# Sound.net
KiCad netlist of a schematic drawn in EAGLE
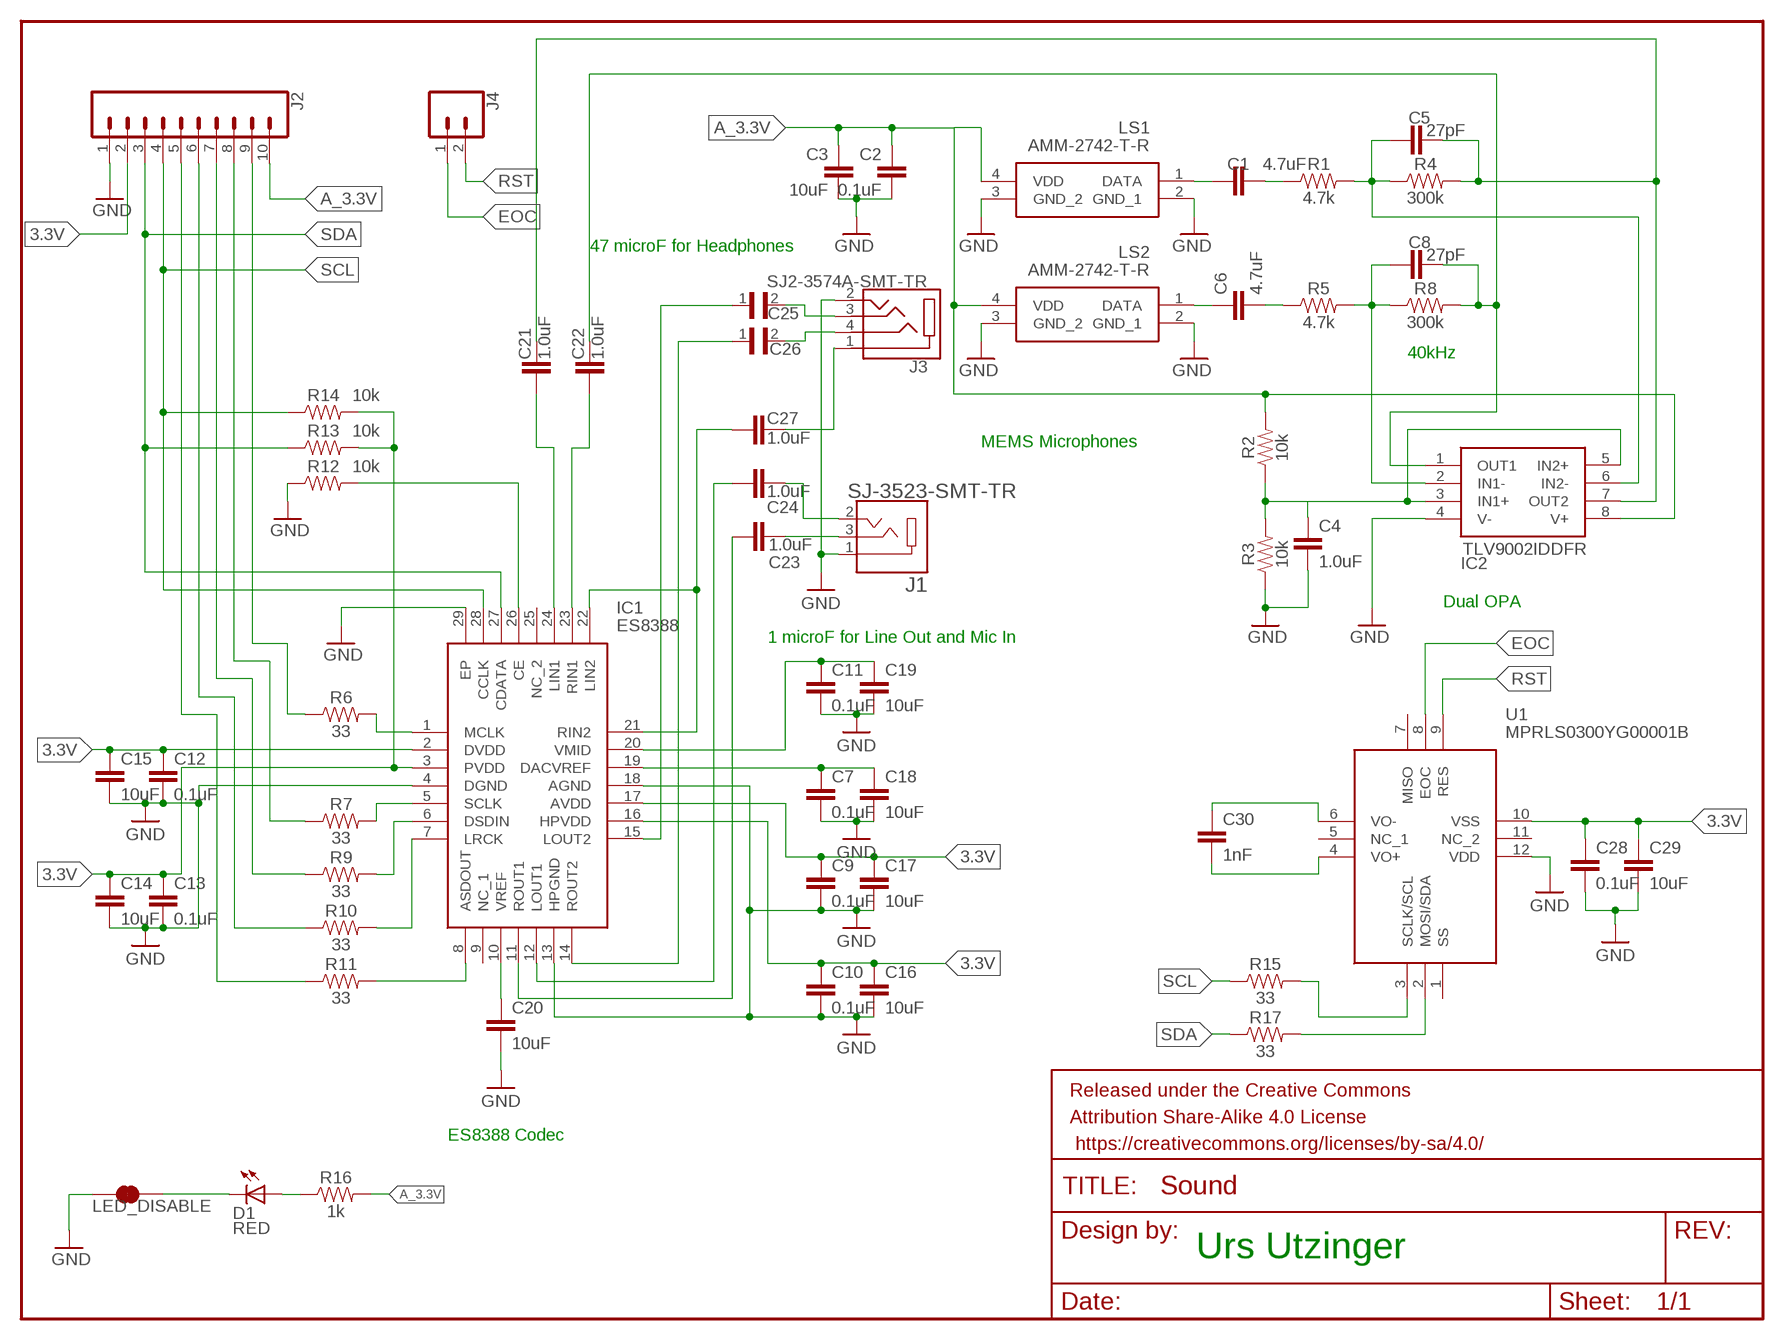
[diagram p0: schematic, sheet 1]

(export (version "E")
  (design (tool "Eeschema 10.0.6"))
  (components
    (comp (ref "C1")
      (value "4.7uF")
      (footprint "eagle-import:0603")
      (libsource (lib "eagle-import") (part "4.7UF-0603-6.3V-(10%)"))
    )
    (comp (ref "C2")
      (value "0.1uF")
      (footprint "eagle-import:0603")
      (libsource (lib "eagle-import") (part "0.1UF-0603-25V-5%"))
    )
    (comp (ref "C3")
      (value "10uF")
      (footprint "eagle-import:0603")
      (libsource (lib "eagle-import") (part "10UF-0603-6.3V-20%"))
    )
    (comp (ref "C4")
      (value "1.0uF")
      (footprint "eagle-import:0603")
      (libsource (lib "eagle-import") (part "1.0UF-0603-16V-10%"))
    )
    (comp (ref "C5")
      (value "27pF")
      (footprint "eagle-import:0603")
      (libsource (lib "eagle-import") (part "27PF-0603-50V-5%"))
    )
    (comp (ref "C6")
      (value "4.7uF")
      (footprint "eagle-import:0603")
      (libsource (lib "eagle-import") (part "4.7UF-0603-6.3V-(10%)"))
    )
    (comp (ref "C7")
      (value "0.1uF")
      (footprint "eagle-import:0603")
      (libsource (lib "eagle-import") (part "0.1UF-0603-25V-5%"))
    )
    (comp (ref "C8")
      (value "27pF")
      (footprint "eagle-import:0603")
      (libsource (lib "eagle-import") (part "27PF-0603-50V-5%"))
    )
    (comp (ref "C9")
      (value "0.1uF")
      (footprint "eagle-import:0603")
      (libsource (lib "eagle-import") (part "0.1UF-0603-25V-5%"))
    )
    (comp (ref "C10")
      (value "0.1uF")
      (footprint "eagle-import:0603")
      (libsource (lib "eagle-import") (part "0.1UF-0603-25V-5%"))
    )
    (comp (ref "C11")
      (value "0.1uF")
      (footprint "eagle-import:0603")
      (libsource (lib "eagle-import") (part "0.1UF-0603-25V-5%"))
    )
    (comp (ref "C12")
      (value "0.1uF")
      (footprint "eagle-import:0603")
      (libsource (lib "eagle-import") (part "0.1UF-0603-25V-5%"))
    )
    (comp (ref "C13")
      (value "0.1uF")
      (footprint "eagle-import:0603")
      (libsource (lib "eagle-import") (part "0.1UF-0603-25V-5%"))
    )
    (comp (ref "C14")
      (value "10uF")
      (footprint "eagle-import:0603")
      (libsource (lib "eagle-import") (part "10UF-0603-6.3V-20%"))
    )
    (comp (ref "C15")
      (value "10uF")
      (footprint "eagle-import:0603")
      (libsource (lib "eagle-import") (part "10UF-0603-6.3V-20%"))
    )
    (comp (ref "C16")
      (value "10uF")
      (footprint "eagle-import:0603")
      (libsource (lib "eagle-import") (part "10UF-0603-6.3V-20%"))
    )
    (comp (ref "C17")
      (value "10uF")
      (footprint "eagle-import:0603")
      (libsource (lib "eagle-import") (part "10UF-0603-6.3V-20%"))
    )
    (comp (ref "C18")
      (value "10uF")
      (footprint "eagle-import:0603")
      (libsource (lib "eagle-import") (part "10UF-0603-6.3V-20%"))
    )
    (comp (ref "C19")
      (value "10uF")
      (footprint "eagle-import:0603")
      (libsource (lib "eagle-import") (part "10UF-0603-6.3V-20%"))
    )
    (comp (ref "C20")
      (value "10uF")
      (footprint "eagle-import:0603")
      (libsource (lib "eagle-import") (part "10UF-0603-6.3V-20%"))
    )
    (comp (ref "C21")
      (value "1.0uF")
      (footprint "eagle-import:0603")
      (libsource (lib "eagle-import") (part "1.0UF-0603-16V-10%"))
    )
    (comp (ref "C22")
      (value "1.0uF")
      (footprint "eagle-import:0603")
      (libsource (lib "eagle-import") (part "1.0UF-0603-16V-10%"))
    )
    (comp (ref "C23")
      (value "1.0uF")
      (footprint "eagle-import:0603")
      (libsource (lib "eagle-import") (part "1.0UF-0603-16V-10%"))
    )
    (comp (ref "C24")
      (value "1.0uF")
      (footprint "eagle-import:0603")
      (libsource (lib "eagle-import") (part "1.0UF-0603-16V-10%"))
    )
    (comp (ref "C25")
      (value "GRM188R60J476ME15D")
      (footprint "eagle-import:CAPC1608X100N")
      (libsource (lib "eagle-import") (part "GRM188R60J476ME15D"))
    )
    (comp (ref "C26")
      (value "GRM188R60J476ME15D")
      (footprint "eagle-import:CAPC1608X100N")
      (libsource (lib "eagle-import") (part "GRM188R60J476ME15D"))
    )
    (comp (ref "C27")
      (value "1.0uF")
      (footprint "eagle-import:0603")
      (libsource (lib "eagle-import") (part "1.0UF-0603-16V-10%"))
    )
    (comp (ref "C28")
      (value "0.1uF")
      (footprint "eagle-import:0603")
      (libsource (lib "eagle-import") (part "0.1UF-0603-25V-5%"))
    )
    (comp (ref "C29")
      (value "10uF")
      (footprint "eagle-import:0603")
      (libsource (lib "eagle-import") (part "10UF-0603-6.3V-20%"))
    )
    (comp (ref "C30")
      (value "1nF")
      (footprint "eagle-import:0603")
      (libsource (lib "eagle-import") (part "1.0NF/1000PF-0603-50V-10%"))
    )
    (comp (ref "D1")
      (value "RED")
      (footprint "eagle-import:LED-0603")
      (libsource (lib "eagle-import") (part "LED-RED0603"))
    )
    (comp (ref "FRAME1")
      (value "FRAME-LETTERNO_PACKAGE")
      (footprint "eagle-import:DUMMY")
      (fields (field (name "DESIGNER") "Nobody"))
      (libsource (lib "eagle-import") (part "FRAME-LETTERNO_PACKAGE"))
    )
    (comp (ref "IC1")
      (value "ES8388")
      (footprint "eagle-import:QFN45P400X400X90-29N")
      (libsource (lib "eagle-import") (part "ES8388"))
    )
    (comp (ref "IC2")
      (value "TLV9002IDDFR")
      (footprint "eagle-import:SOT65P280X110-8N")
      (fields (field (name "MOUSER_PART_NUMBER") "595-TLV9002IDDFR"))
      (libsource (lib "eagle-import") (part "TLV9002IDDFR"))
    )
    (comp (ref "J1")
      (value "SJ-3523-SMT-TR")
      (footprint "eagle-import:CUI_SJ-3523-SMT-TR")
      (fields (field (name "MF") "CUI Inc"))
      (libsource (lib "eagle-import") (part "SJ-3523-SMT-TR"))
    )
    (comp (ref "J2")
      (value "CONN_10\"")
      (footprint "eagle-import:1X10")
      (libsource (lib "eagle-import") (part "CONN_10{dblquote}"))
    )
    (comp (ref "J3")
      (value "SJ2-3574A-SMT-TR")
      (footprint "eagle-import:CUI_SJ2-3574A-SMT-TR")
      (fields (field (name "MANUFACTURER") "CUI"))
      (libsource (lib "eagle-import") (part "SJ2-3574A-SMT-TR"))
    )
    (comp (ref "J4")
      (value "CONN_02")
      (footprint "eagle-import:1X02")
      (libsource (lib "eagle-import") (part "CONN_02"))
    )
    (comp (ref "LED_DISABLE")
      (value "JUMPER-SMT_2_NC_TRACE_SILK")
      (footprint "eagle-import:SMT-JUMPER_2_NC_TRACE_SILK")
      (libsource (lib "eagle-import") (part "JUMPER-SMT_2_NC_TRACE_SILK"))
    )
    (comp (ref "LS1")
      (value "AMM-2742-T-R")
      (footprint "eagle-import:AMM2742TR")
      (fields (field (name "MOUSER_PART_NUMBER") "665-AMM-2742-T-R"))
      (libsource (lib "eagle-import") (part "AMM-2742-T-R"))
    )
    (comp (ref "LS2")
      (value "AMM-2742-T-R")
      (footprint "eagle-import:AMM2742TR")
      (fields (field (name "MOUSER_PART_NUMBER") "665-AMM-2742-T-R"))
      (libsource (lib "eagle-import") (part "AMM-2742-T-R"))
    )
    (comp (ref "R1")
      (value "4.7k")
      (footprint "eagle-import:0603")
      (libsource (lib "eagle-import") (part "4.7KOHM-0603-1/10W-1%"))
    )
    (comp (ref "R2")
      (value "10k")
      (footprint "eagle-import:0603")
      (libsource (lib "eagle-import") (part "10KOHM-0603-1/10W-1%"))
    )
    (comp (ref "R3")
      (value "10k")
      (footprint "eagle-import:0603")
      (libsource (lib "eagle-import") (part "10KOHM-0603-1/10W-1%"))
    )
    (comp (ref "R4")
      (value "300k")
      (footprint "eagle-import:0603")
      (libsource (lib "eagle-import") (part "300KOHM-0603-1/10W-1%"))
    )
    (comp (ref "R5")
      (value "4.7k")
      (footprint "eagle-import:0603")
      (libsource (lib "eagle-import") (part "4.7KOHM-0603-1/10W-1%"))
    )
    (comp (ref "R6")
      (value "33")
      (footprint "eagle-import:0603")
      (libsource (lib "eagle-import") (part "33OHM-0603-1/10W-1%"))
    )
    (comp (ref "R7")
      (value "33")
      (footprint "eagle-import:0603")
      (libsource (lib "eagle-import") (part "33OHM-0603-1/10W-1%"))
    )
    (comp (ref "R8")
      (value "300k")
      (footprint "eagle-import:0603")
      (libsource (lib "eagle-import") (part "300KOHM-0603-1/10W-1%"))
    )
    (comp (ref "R9")
      (value "33")
      (footprint "eagle-import:0603")
      (libsource (lib "eagle-import") (part "33OHM-0603-1/10W-1%"))
    )
    (comp (ref "R10")
      (value "33")
      (footprint "eagle-import:0603")
      (libsource (lib "eagle-import") (part "33OHM-0603-1/10W-1%"))
    )
    (comp (ref "R11")
      (value "33")
      (footprint "eagle-import:0603")
      (libsource (lib "eagle-import") (part "33OHM-0603-1/10W-1%"))
    )
    (comp (ref "R12")
      (value "10k")
      (footprint "eagle-import:0603")
      (libsource (lib "eagle-import") (part "10KOHM-0603-1/10W-1%"))
    )
    (comp (ref "R13")
      (value "10k")
      (footprint "eagle-import:0603")
      (libsource (lib "eagle-import") (part "10KOHM-0603-1/10W-1%"))
    )
    (comp (ref "R14")
      (value "10k")
      (footprint "eagle-import:0603")
      (libsource (lib "eagle-import") (part "10KOHM-0603-1/10W-1%"))
    )
    (comp (ref "R15")
      (value "33")
      (footprint "eagle-import:0603")
      (libsource (lib "eagle-import") (part "33OHM-0603-1/10W-1%"))
    )
    (comp (ref "R16")
      (value "1k")
      (footprint "eagle-import:0603")
      (libsource (lib "eagle-import") (part "1KOHM-0603-1/10W-1%"))
    )
    (comp (ref "R17")
      (value "33")
      (footprint "eagle-import:0603")
      (libsource (lib "eagle-import") (part "33OHM-0603-1/10W-1%"))
    )
    (comp (ref "U1")
      (value "MPRLS0300YG00001B")
      (footprint "eagle-import:MPRLS0300YG00001B")
      (fields (field (name "MOUSER_PART_NUMBER") "785-MPRLS0300YG0001B"))
      (libsource (lib "eagle-import") (part "MPRLS0300YG00001B"))
    )
  )
  (nets
    (net (code "1") (name "3.3V") (class "Default")
      (node (ref "C10") (pin "1") (pinfunction "1_1") (pintype "passive"))
      (node (ref "C12") (pin "1") (pinfunction "1_1") (pintype "passive"))
      (node (ref "C13") (pin "1") (pinfunction "1_1") (pintype "passive"))
      (node (ref "C14") (pin "1") (pinfunction "1_1") (pintype "passive"))
      (node (ref "C15") (pin "1") (pinfunction "1_1") (pintype "passive"))
      (node (ref "C16") (pin "1") (pinfunction "1_1") (pintype "passive"))
      (node (ref "C17") (pin "1") (pinfunction "1_1") (pintype "passive"))
      (node (ref "C28") (pin "1") (pinfunction "1_1") (pintype "passive"))
      (node (ref "C29") (pin "1") (pinfunction "1_1") (pintype "passive"))
      (node (ref "C9") (pin "1") (pinfunction "1_1") (pintype "passive"))
      (node (ref "IC1") (pin "16") (pinfunction "HPVDD_16") (pintype "bidirectional"))
      (node (ref "IC1") (pin "17") (pinfunction "AVDD_17") (pintype "bidirectional"))
      (node (ref "IC1") (pin "2") (pinfunction "DVDD_2") (pintype "bidirectional"))
      (node (ref "IC1") (pin "3") (pinfunction "PVDD_3") (pintype "bidirectional"))
      (node (ref "J2") (pin "2") (pinfunction "2_2") (pintype "passive"))
      (node (ref "R13") (pin "2") (pinfunction "2_2") (pintype "passive"))
      (node (ref "R14") (pin "2") (pinfunction "2_2") (pintype "passive"))
      (node (ref "U1") (pin "10") (pinfunction "VSS_10") (pintype "bidirectional"))
    )
    (net (code "2") (name "A_3.3V") (class "Default")
      (node (ref "C2") (pin "1") (pinfunction "1_1") (pintype "passive"))
      (node (ref "C3") (pin "1") (pinfunction "1_1") (pintype "passive"))
      (node (ref "IC2") (pin "8") (pinfunction "V+_8") (pintype "bidirectional"))
      (node (ref "J2") (pin "10") (pinfunction "10_10") (pintype "passive"))
      (node (ref "LS1") (pin "4") (pinfunction "VDD_4") (pintype "bidirectional"))
      (node (ref "LS2") (pin "4") (pinfunction "VDD_4") (pintype "bidirectional"))
      (node (ref "R16") (pin "2") (pinfunction "2_2") (pintype "passive"))
      (node (ref "R2") (pin "2") (pinfunction "2_2") (pintype "passive"))
    )
    (net (code "3") (name "EOC") (class "Default")
      (node (ref "J4") (pin "1") (pinfunction "1_1") (pintype "passive"))
      (node (ref "U1") (pin "8") (pinfunction "EOC_8") (pintype "bidirectional"))
    )
    (net (code "4") (name "GND") (class "Default")
      (node (ref "C10") (pin "2") (pinfunction "2_2") (pintype "passive"))
      (node (ref "C11") (pin "2") (pinfunction "2_2") (pintype "passive"))
      (node (ref "C12") (pin "2") (pinfunction "2_2") (pintype "passive"))
      (node (ref "C13") (pin "2") (pinfunction "2_2") (pintype "passive"))
      (node (ref "C14") (pin "2") (pinfunction "2_2") (pintype "passive"))
      (node (ref "C15") (pin "2") (pinfunction "2_2") (pintype "passive"))
      (node (ref "C16") (pin "2") (pinfunction "2_2") (pintype "passive"))
      (node (ref "C17") (pin "2") (pinfunction "2_2") (pintype "passive"))
      (node (ref "C18") (pin "2") (pinfunction "2_2") (pintype "passive"))
      (node (ref "C19") (pin "2") (pinfunction "2_2") (pintype "passive"))
      (node (ref "C2") (pin "2") (pinfunction "2_2") (pintype "passive"))
      (node (ref "C20") (pin "2") (pinfunction "2_2") (pintype "passive"))
      (node (ref "C28") (pin "2") (pinfunction "2_2") (pintype "passive"))
      (node (ref "C29") (pin "2") (pinfunction "2_2") (pintype "passive"))
      (node (ref "C3") (pin "2") (pinfunction "2_2") (pintype "passive"))
      (node (ref "C4") (pin "2") (pinfunction "2_2") (pintype "passive"))
      (node (ref "C7") (pin "2") (pinfunction "2_2") (pintype "passive"))
      (node (ref "C9") (pin "2") (pinfunction "2_2") (pintype "passive"))
      (node (ref "IC1") (pin "13") (pinfunction "HPGND_13") (pintype "bidirectional"))
      (node (ref "IC1") (pin "18") (pinfunction "AGND_18") (pintype "bidirectional"))
      (node (ref "IC1") (pin "29") (pinfunction "EP_29") (pintype "bidirectional"))
      (node (ref "IC1") (pin "4") (pinfunction "DGND_4") (pintype "bidirectional"))
      (node (ref "IC2") (pin "4") (pinfunction "V-_4") (pintype "bidirectional"))
      (node (ref "J1") (pin "1") (pinfunction "1_1") (pintype "passive"))
      (node (ref "J2") (pin "1") (pinfunction "1_1") (pintype "passive"))
      (node (ref "J3") (pin "2") (pinfunction "2_2") (pintype "passive"))
      (node (ref "LED_DISABLE") (pin "1") (pinfunction "1_1") (pintype "passive"))
      (node (ref "LS1") (pin "2") (pinfunction "GND_1_2") (pintype "bidirectional"))
      (node (ref "LS1") (pin "3") (pinfunction "GND_2_3") (pintype "bidirectional"))
      (node (ref "LS2") (pin "2") (pinfunction "GND_1_2") (pintype "bidirectional"))
      (node (ref "LS2") (pin "3") (pinfunction "GND_2_3") (pintype "bidirectional"))
      (node (ref "R12") (pin "1") (pinfunction "1_1") (pintype "passive"))
      (node (ref "R3") (pin "1") (pinfunction "1_1") (pintype "passive"))
      (node (ref "U1") (pin "12") (pinfunction "VDD_12") (pintype "bidirectional"))
    )
    (net (code "5") (name "Net-(C1-Pad2)") (class "Default")
      (node (ref "C1") (pin "2") (pinfunction "2_2") (pintype "passive"))
      (node (ref "R1") (pin "1") (pinfunction "1_1") (pintype "passive"))
    )
    (net (code "6") (name "Net-(C6-Pad2)") (class "Default")
      (node (ref "C6") (pin "2") (pinfunction "2_2") (pintype "passive"))
      (node (ref "R5") (pin "1") (pinfunction "1_1") (pintype "passive"))
    )
    (net (code "7") (name "Net-(C23-Pad1)") (class "Default")
      (node (ref "C23") (pin "1") (pinfunction "1_1") (pintype "passive"))
      (node (ref "J1") (pin "3") (pinfunction "3_3") (pintype "passive"))
    )
    (net (code "8") (name "Net-(C24-Pad1)") (class "Default")
      (node (ref "C24") (pin "1") (pinfunction "1_1") (pintype "passive"))
      (node (ref "J1") (pin "2") (pinfunction "2_2") (pintype "passive"))
    )
    (net (code "9") (name "Net-(C25-Pad2)") (class "Default")
      (node (ref "C25") (pin "2") (pinfunction "2_2") (pintype "passive"))
      (node (ref "J3") (pin "3") (pinfunction "3_3") (pintype "passive"))
    )
    (net (code "10") (name "Net-(C26-Pad2)") (class "Default")
      (node (ref "C26") (pin "2") (pinfunction "2_2") (pintype "passive"))
      (node (ref "J3") (pin "4") (pinfunction "4_4") (pintype "passive"))
    )
    (net (code "11") (name "Net-(C27-Pad2)") (class "Default")
      (node (ref "C27") (pin "2") (pinfunction "2_2") (pintype "passive"))
      (node (ref "J3") (pin "1") (pinfunction "1_1") (pintype "passive"))
    )
    (net (code "12") (name "Net-(D1-PadA)") (class "Default")
      (node (ref "D1") (pin "A") (pinfunction "A_A") (pintype "passive"))
      (node (ref "R16") (pin "1") (pinfunction "1_1") (pintype "passive"))
    )
    (net (code "13") (name "Net-(D1-PadC)") (class "Default")
      (node (ref "D1") (pin "C") (pinfunction "C_C") (pintype "passive"))
      (node (ref "LED_DISABLE") (pin "2") (pinfunction "2_2") (pintype "passive"))
    )
    (net (code "14") (name "Net-(IC1-ASDOUT)") (class "Default")
      (node (ref "IC1") (pin "8") (pinfunction "ASDOUT_8") (pintype "bidirectional"))
      (node (ref "R11") (pin "2") (pinfunction "2_2") (pintype "passive"))
    )
    (net (code "15") (name "Net-(IC1-CE)") (class "Default")
      (node (ref "IC1") (pin "26") (pinfunction "CE_26") (pintype "bidirectional"))
      (node (ref "R12") (pin "2") (pinfunction "2_2") (pintype "passive"))
    )
    (net (code "16") (name "Net-(IC1-DACVREF)") (class "Default")
      (node (ref "C18") (pin "1") (pinfunction "1_1") (pintype "passive"))
      (node (ref "C7") (pin "1") (pinfunction "1_1") (pintype "passive"))
      (node (ref "IC1") (pin "19") (pinfunction "DACVREF_19") (pintype "bidirectional"))
    )
    (net (code "17") (name "Net-(IC1-DSDIN)") (class "Default")
      (node (ref "IC1") (pin "6") (pinfunction "DSDIN_6") (pintype "bidirectional"))
      (node (ref "R9") (pin "2") (pinfunction "2_2") (pintype "passive"))
    )
    (net (code "18") (name "Net-(IC1-LIN1)") (class "Default")
      (node (ref "C21") (pin "1") (pinfunction "1_1") (pintype "passive"))
      (node (ref "IC1") (pin "24") (pinfunction "LIN1_24") (pintype "bidirectional"))
    )
    (net (code "19") (name "Net-(IC1-LIN2)") (class "Default")
      (node (ref "C27") (pin "1") (pinfunction "1_1") (pintype "passive"))
      (node (ref "IC1") (pin "21") (pinfunction "RIN2_21") (pintype "bidirectional"))
      (node (ref "IC1") (pin "22") (pinfunction "LIN2_22") (pintype "bidirectional"))
    )
    (net (code "20") (name "Net-(IC1-LOUT1)") (class "Default")
      (node (ref "C24") (pin "2") (pinfunction "2_2") (pintype "passive"))
      (node (ref "IC1") (pin "12") (pinfunction "LOUT1_12") (pintype "bidirectional"))
    )
    (net (code "21") (name "Net-(IC1-LOUT2)") (class "Default")
      (node (ref "C25") (pin "1") (pinfunction "1_1") (pintype "passive"))
      (node (ref "IC1") (pin "15") (pinfunction "LOUT2_15") (pintype "bidirectional"))
    )
    (net (code "22") (name "Net-(IC1-LRCK)") (class "Default")
      (node (ref "IC1") (pin "7") (pinfunction "LRCK_7") (pintype "bidirectional"))
      (node (ref "R10") (pin "2") (pinfunction "2_2") (pintype "passive"))
    )
    (net (code "23") (name "Net-(IC1-MCLK)") (class "Default")
      (node (ref "IC1") (pin "1") (pinfunction "MCLK_1") (pintype "bidirectional"))
      (node (ref "R6") (pin "2") (pinfunction "2_2") (pintype "passive"))
    )
    (net (code "24") (name "Net-(IC1-RIN1)") (class "Default")
      (node (ref "C22") (pin "1") (pinfunction "1_1") (pintype "passive"))
      (node (ref "IC1") (pin "23") (pinfunction "RIN1_23") (pintype "bidirectional"))
    )
    (net (code "25") (name "Net-(IC1-ROUT1)") (class "Default")
      (node (ref "C23") (pin "2") (pinfunction "2_2") (pintype "passive"))
      (node (ref "IC1") (pin "11") (pinfunction "ROUT1_11") (pintype "bidirectional"))
    )
    (net (code "26") (name "Net-(IC1-ROUT2)") (class "Default")
      (node (ref "C26") (pin "1") (pinfunction "1_1") (pintype "passive"))
      (node (ref "IC1") (pin "14") (pinfunction "ROUT2_14") (pintype "bidirectional"))
    )
    (net (code "27") (name "Net-(IC1-SCLK)") (class "Default")
      (node (ref "IC1") (pin "5") (pinfunction "SCLK_5") (pintype "bidirectional"))
      (node (ref "R7") (pin "2") (pinfunction "2_2") (pintype "passive"))
    )
    (net (code "28") (name "Net-(IC1-VMID)") (class "Default")
      (node (ref "C11") (pin "1") (pinfunction "1_1") (pintype "passive"))
      (node (ref "C19") (pin "1") (pinfunction "1_1") (pintype "passive"))
      (node (ref "IC1") (pin "20") (pinfunction "VMID_20") (pintype "bidirectional"))
    )
    (net (code "29") (name "Net-(IC1-VREF)") (class "Default")
      (node (ref "C20") (pin "1") (pinfunction "1_1") (pintype "passive"))
      (node (ref "IC1") (pin "10") (pinfunction "VREF_10") (pintype "bidirectional"))
    )
    (net (code "30") (name "Net-(IC2-IN1+)") (class "Default")
      (node (ref "C4") (pin "1") (pinfunction "1_1") (pintype "passive"))
      (node (ref "IC2") (pin "3") (pinfunction "IN1+_3") (pintype "bidirectional"))
      (node (ref "IC2") (pin "5") (pinfunction "IN2+_5") (pintype "bidirectional"))
      (node (ref "R2") (pin "1") (pinfunction "1_1") (pintype "passive"))
      (node (ref "R3") (pin "2") (pinfunction "2_2") (pintype "passive"))
    )
    (net (code "31") (name "Net-(IC2-IN1-)") (class "Default")
      (node (ref "C8") (pin "1") (pinfunction "1_1") (pintype "passive"))
      (node (ref "IC2") (pin "2") (pinfunction "IN1-_2") (pintype "bidirectional"))
      (node (ref "R5") (pin "2") (pinfunction "2_2") (pintype "passive"))
      (node (ref "R8") (pin "1") (pinfunction "1_1") (pintype "passive"))
    )
    (net (code "32") (name "Net-(IC2-IN2-)") (class "Default")
      (node (ref "C5") (pin "1") (pinfunction "1_1") (pintype "passive"))
      (node (ref "IC2") (pin "6") (pinfunction "IN2-_6") (pintype "bidirectional"))
      (node (ref "R1") (pin "2") (pinfunction "2_2") (pintype "passive"))
      (node (ref "R4") (pin "1") (pinfunction "1_1") (pintype "passive"))
    )
    (net (code "33") (name "Net-(IC2-OUT1)") (class "Default")
      (node (ref "C22") (pin "2") (pinfunction "2_2") (pintype "passive"))
      (node (ref "C8") (pin "2") (pinfunction "2_2") (pintype "passive"))
      (node (ref "IC2") (pin "1") (pinfunction "OUT1_1") (pintype "bidirectional"))
      (node (ref "R8") (pin "2") (pinfunction "2_2") (pintype "passive"))
    )
    (net (code "34") (name "Net-(IC2-OUT2)") (class "Default")
      (node (ref "C21") (pin "2") (pinfunction "2_2") (pintype "passive"))
      (node (ref "C5") (pin "2") (pinfunction "2_2") (pintype "passive"))
      (node (ref "IC2") (pin "7") (pinfunction "OUT2_7") (pintype "bidirectional"))
      (node (ref "R4") (pin "2") (pinfunction "2_2") (pintype "passive"))
    )
    (net (code "35") (name "Net-(J2-Pad5)") (class "Default")
      (node (ref "J2") (pin "5") (pinfunction "5_5") (pintype "passive"))
      (node (ref "R11") (pin "1") (pinfunction "1_1") (pintype "passive"))
    )
    (net (code "36") (name "Net-(J2-Pad6)") (class "Default")
      (node (ref "J2") (pin "6") (pinfunction "6_6") (pintype "passive"))
      (node (ref "R10") (pin "1") (pinfunction "1_1") (pintype "passive"))
    )
    (net (code "37") (name "Net-(J2-Pad7)") (class "Default")
      (node (ref "J2") (pin "7") (pinfunction "7_7") (pintype "passive"))
      (node (ref "R9") (pin "1") (pinfunction "1_1") (pintype "passive"))
    )
    (net (code "38") (name "Net-(J2-Pad8)") (class "Default")
      (node (ref "J2") (pin "8") (pinfunction "8_8") (pintype "passive"))
      (node (ref "R7") (pin "1") (pinfunction "1_1") (pintype "passive"))
    )
    (net (code "39") (name "Net-(J2-Pad9)") (class "Default")
      (node (ref "J2") (pin "9") (pinfunction "9_9") (pintype "passive"))
      (node (ref "R6") (pin "1") (pinfunction "1_1") (pintype "passive"))
    )
    (net (code "40") (name "Net-(LS1-DATA)") (class "Default")
      (node (ref "C1") (pin "1") (pinfunction "1_1") (pintype "passive"))
      (node (ref "LS1") (pin "1") (pinfunction "DATA_1") (pintype "bidirectional"))
    )
    (net (code "41") (name "Net-(LS2-DATA)") (class "Default")
      (node (ref "C6") (pin "1") (pinfunction "1_1") (pintype "passive"))
      (node (ref "LS2") (pin "1") (pinfunction "DATA_1") (pintype "bidirectional"))
    )
    (net (code "42") (name "Net-(U1-MOSI{slash}SDA)") (class "Default")
      (node (ref "R17") (pin "2") (pinfunction "2_2") (pintype "passive"))
      (node (ref "U1") (pin "2") (pinfunction "MOSI/SDA_2") (pintype "bidirectional"))
    )
    (net (code "43") (name "Net-(U1-SCLK{slash}SCL)") (class "Default")
      (node (ref "R15") (pin "2") (pinfunction "2_2") (pintype "passive"))
      (node (ref "U1") (pin "3") (pinfunction "SCLK/SCL_3") (pintype "bidirectional"))
    )
    (net (code "44") (name "Net-(U1-VO+)") (class "Default")
      (node (ref "C30") (pin "2") (pinfunction "2_2") (pintype "passive"))
      (node (ref "U1") (pin "4") (pinfunction "VO+_4") (pintype "bidirectional"))
    )
    (net (code "45") (name "Net-(U1-VO-)") (class "Default")
      (node (ref "C30") (pin "1") (pinfunction "1_1") (pintype "passive"))
      (node (ref "U1") (pin "6") (pinfunction "VO-_6") (pintype "bidirectional"))
    )
    (net (code "46") (name "RST") (class "Default")
      (node (ref "J4") (pin "2") (pinfunction "2_2") (pintype "passive"))
      (node (ref "U1") (pin "9") (pinfunction "RES_9") (pintype "bidirectional"))
    )
    (net (code "47") (name "SCL") (class "Default")
      (node (ref "IC1") (pin "28") (pinfunction "CCLK_28") (pintype "bidirectional"))
      (node (ref "J2") (pin "4") (pinfunction "4_4") (pintype "passive"))
      (node (ref "R14") (pin "1") (pinfunction "1_1") (pintype "passive"))
      (node (ref "R15") (pin "1") (pinfunction "1_1") (pintype "passive"))
    )
    (net (code "48") (name "SDA") (class "Default")
      (node (ref "IC1") (pin "27") (pinfunction "CDATA_27") (pintype "bidirectional"))
      (node (ref "J2") (pin "3") (pinfunction "3_3") (pintype "passive"))
      (node (ref "R13") (pin "1") (pinfunction "1_1") (pintype "passive"))
      (node (ref "R17") (pin "1") (pinfunction "1_1") (pintype "passive"))
    )
    (net (code "49") (name "unconnected-(IC1-NC_1-Pad9)") (class "Default")
      (node (ref "IC1") (pin "9") (pinfunction "NC_1_9") (pintype "bidirectional"))
    )
    (net (code "50") (name "unconnected-(IC1-NC_2-Pad25)") (class "Default")
      (node (ref "IC1") (pin "25") (pinfunction "NC_2_25") (pintype "bidirectional"))
    )
    (net (code "51") (name "unconnected-(U1-MISO-Pad7)") (class "Default")
      (node (ref "U1") (pin "7") (pinfunction "MISO_7") (pintype "bidirectional"))
    )
    (net (code "52") (name "unconnected-(U1-NC_1-Pad5)") (class "Default")
      (node (ref "U1") (pin "5") (pinfunction "NC_1_5") (pintype "bidirectional"))
    )
    (net (code "53") (name "unconnected-(U1-NC_2-Pad11)") (class "Default")
      (node (ref "U1") (pin "11") (pinfunction "NC_2_11") (pintype "bidirectional"))
    )
    (net (code "54") (name "unconnected-(U1-SS-Pad1)") (class "Default")
      (node (ref "U1") (pin "1") (pinfunction "SS_1") (pintype "bidirectional"))
    )
  )
)
